# markIII_adapter.net
KiCad netlist of a schematic drawn in EAGLE
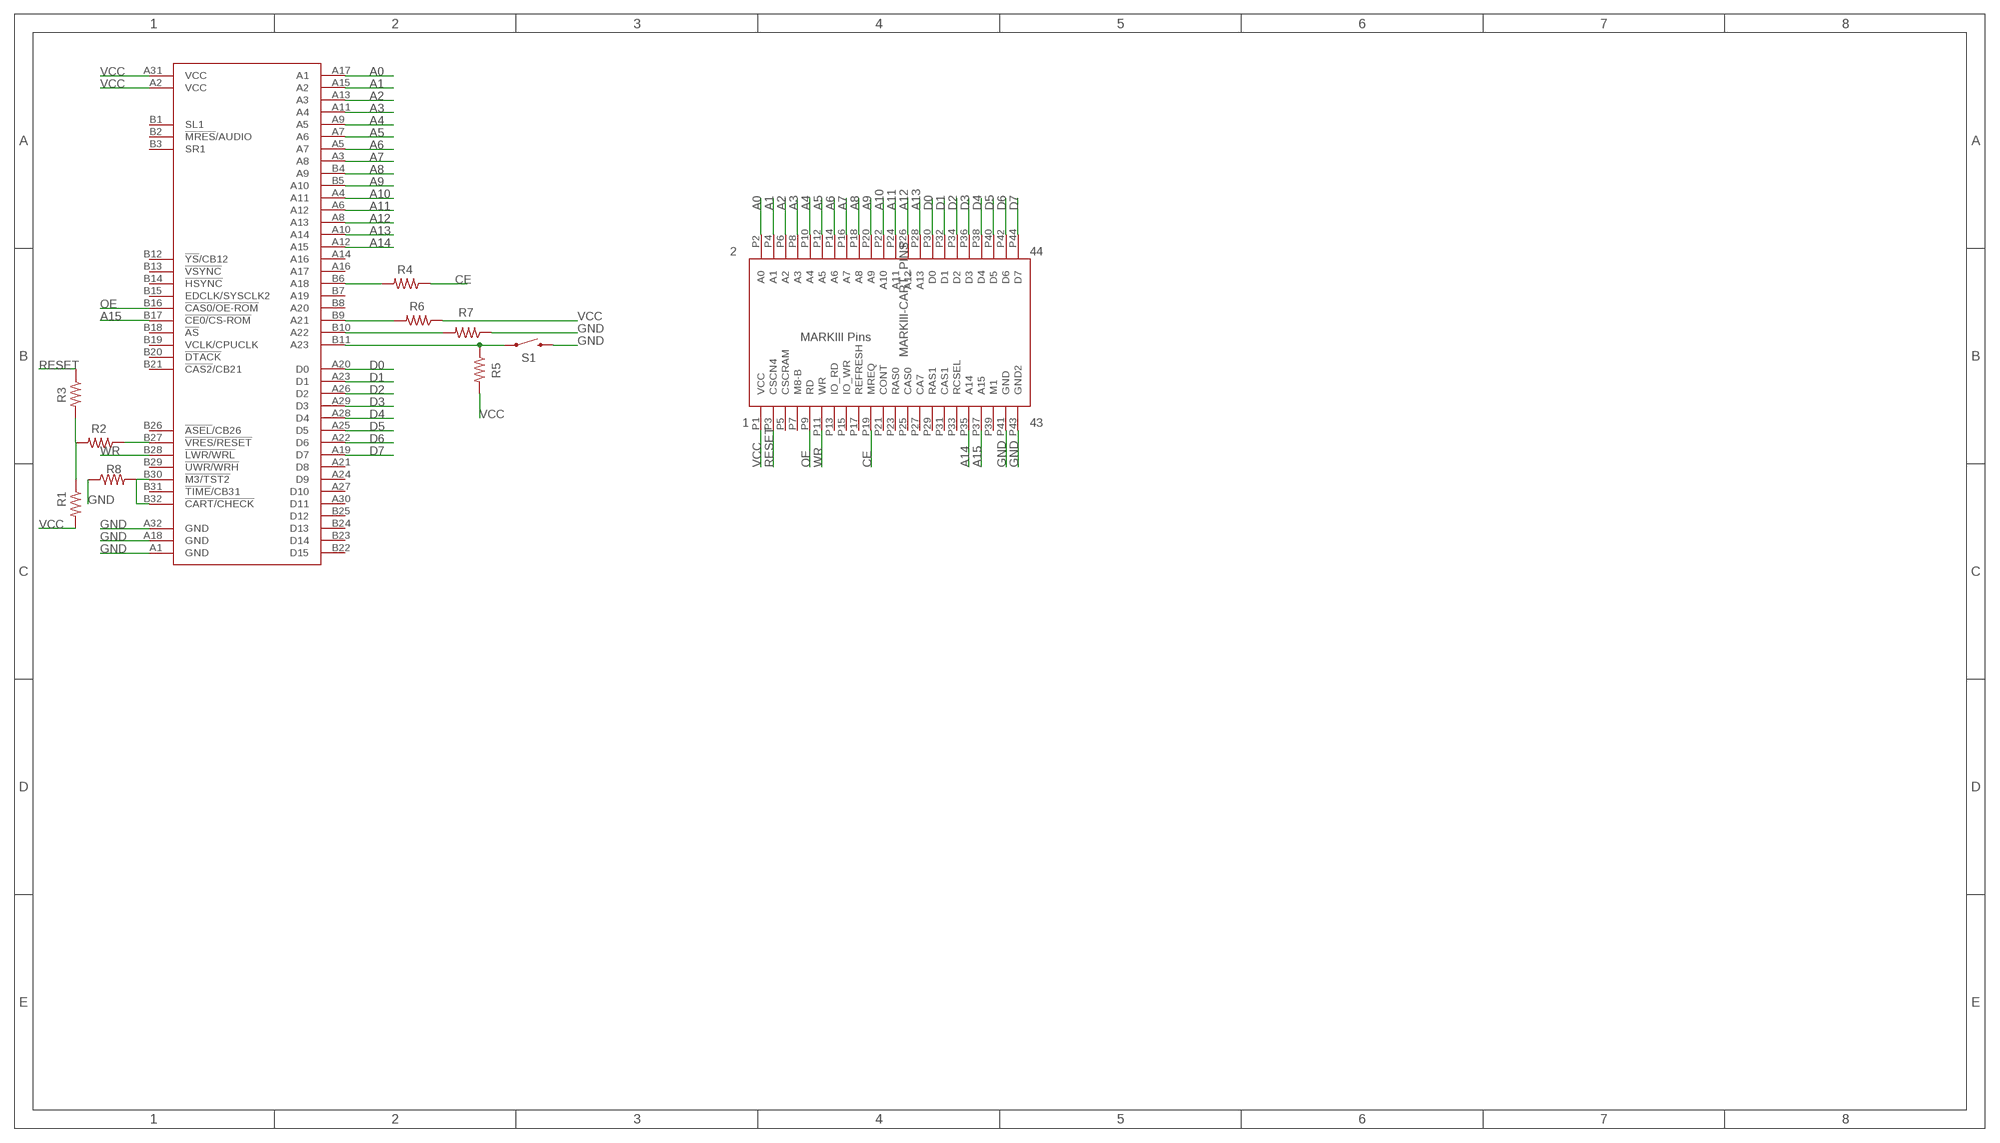
[diagram p0: schematic, sheet 1]

(export (version "E")
  (design (tool "Eeschema 10.0.6"))
  (components
    (comp (ref "CN3")
      (value "MEGADRIVE-CART-CONNECTOR-ORDERED")
      (footprint "eagle-import:MEGADRIVE-CART-CONNECTOR")
      (libsource (lib "eagle-import") (part "MEGADRIVE-CART-CONNECTOR-ORDERED"))
    )
    (comp (ref "R1")
      (value "0")
      (footprint "eagle-import:M1206")
      (libsource (lib "eagle-import") (part "R-US_M1206"))
    )
    (comp (ref "R2")
      (value "NP")
      (footprint "eagle-import:M1206")
      (libsource (lib "eagle-import") (part "R-US_M1206"))
    )
    (comp (ref "R3")
      (value "NP")
      (footprint "eagle-import:M1206")
      (libsource (lib "eagle-import") (part "R-US_M1206"))
    )
    (comp (ref "R4")
      (value "0")
      (footprint "eagle-import:M1206")
      (libsource (lib "eagle-import") (part "R-US_M1206"))
    )
    (comp (ref "R5")
      (value "56K")
      (footprint "eagle-import:M1206")
      (libsource (lib "eagle-import") (part "R-US_M1206"))
    )
    (comp (ref "R6")
      (value "0")
      (footprint "eagle-import:M1206")
      (libsource (lib "eagle-import") (part "R-US_M1206"))
    )
    (comp (ref "R7")
      (value "0")
      (footprint "eagle-import:M1206")
      (libsource (lib "eagle-import") (part "R-US_M1206"))
    )
    (comp (ref "R8")
      (value "0")
      (footprint "eagle-import:M1206")
      (libsource (lib "eagle-import") (part "R-US_M1206"))
    )
    (comp (ref "S1")
      (value "MOMENTARY-SWITCH-SPST-SMD-5.2MM")
      (footprint "eagle-import:TACTILE_SWITCH_SMD_5.2MM")
      (libsource (lib "eagle-import") (part "MOMENTARY-SWITCH-SPST-SMD-5.2MM"))
    )
    (comp (ref "U$1")
      (value "MARKIII-CART_PINS")
      (footprint "eagle-import:MARKIII_PINS")
      (libsource (lib "eagle-import") (part "MARKIII-CART_PINS"))
    )
  )
  (nets
    (net (code "1") (name "/A0") (class "Default")
      (node (ref "CN3") (pin "A17") (pinfunction "A1_A17") (pintype "bidirectional"))
      (node (ref "U$1") (pin "P2") (pinfunction "A0_P2") (pintype "bidirectional"))
    )
    (net (code "2") (name "/A1") (class "Default")
      (node (ref "CN3") (pin "A15") (pinfunction "A2_A15") (pintype "bidirectional"))
      (node (ref "U$1") (pin "P4") (pinfunction "A1_P4") (pintype "bidirectional"))
    )
    (net (code "3") (name "/A2") (class "Default")
      (node (ref "CN3") (pin "A13") (pinfunction "A3_A13") (pintype "bidirectional"))
      (node (ref "U$1") (pin "P6") (pinfunction "A2_P6") (pintype "bidirectional"))
    )
    (net (code "4") (name "/A3") (class "Default")
      (node (ref "CN3") (pin "A11") (pinfunction "A4_A11") (pintype "bidirectional"))
      (node (ref "U$1") (pin "P8") (pinfunction "A3_P8") (pintype "bidirectional"))
    )
    (net (code "5") (name "/A4") (class "Default")
      (node (ref "CN3") (pin "A9") (pinfunction "A5_A9") (pintype "bidirectional"))
      (node (ref "U$1") (pin "P10") (pinfunction "A4_P10") (pintype "bidirectional"))
    )
    (net (code "6") (name "/A5") (class "Default")
      (node (ref "CN3") (pin "A7") (pinfunction "A6_A7") (pintype "bidirectional"))
      (node (ref "U$1") (pin "P12") (pinfunction "A5_P12") (pintype "bidirectional"))
    )
    (net (code "7") (name "/A6") (class "Default")
      (node (ref "CN3") (pin "A5") (pinfunction "A7_A5") (pintype "bidirectional"))
      (node (ref "U$1") (pin "P14") (pinfunction "A6_P14") (pintype "bidirectional"))
    )
    (net (code "8") (name "/A7") (class "Default")
      (node (ref "CN3") (pin "A3") (pinfunction "A8_A3") (pintype "bidirectional"))
      (node (ref "U$1") (pin "P16") (pinfunction "A7_P16") (pintype "bidirectional"))
    )
    (net (code "9") (name "/A8") (class "Default")
      (node (ref "CN3") (pin "B4") (pinfunction "A9_B4") (pintype "bidirectional"))
      (node (ref "U$1") (pin "P18") (pinfunction "A8_P18") (pintype "bidirectional"))
    )
    (net (code "10") (name "/A9") (class "Default")
      (node (ref "CN3") (pin "B5") (pinfunction "A10_B5") (pintype "bidirectional"))
      (node (ref "U$1") (pin "P20") (pinfunction "A9_P20") (pintype "bidirectional"))
    )
    (net (code "11") (name "/A10") (class "Default")
      (node (ref "CN3") (pin "A4") (pinfunction "A11_A4") (pintype "bidirectional"))
      (node (ref "U$1") (pin "P22") (pinfunction "A10_P22") (pintype "bidirectional"))
    )
    (net (code "12") (name "/A11") (class "Default")
      (node (ref "CN3") (pin "A6") (pinfunction "A12_A6") (pintype "bidirectional"))
      (node (ref "U$1") (pin "P24") (pinfunction "A11_P24") (pintype "bidirectional"))
    )
    (net (code "13") (name "/A12") (class "Default")
      (node (ref "CN3") (pin "A8") (pinfunction "A13_A8") (pintype "bidirectional"))
      (node (ref "U$1") (pin "P26") (pinfunction "A12_P26") (pintype "bidirectional"))
    )
    (net (code "14") (name "/A13") (class "Default")
      (node (ref "CN3") (pin "A10") (pinfunction "A14_A10") (pintype "bidirectional"))
      (node (ref "U$1") (pin "P28") (pinfunction "A13_P28") (pintype "bidirectional"))
    )
    (net (code "15") (name "/A14") (class "Default")
      (node (ref "CN3") (pin "A12") (pinfunction "A15_A12") (pintype "bidirectional"))
      (node (ref "U$1") (pin "P35") (pinfunction "A14_P35") (pintype "bidirectional"))
    )
    (net (code "16") (name "/A15") (class "Default")
      (node (ref "CN3") (pin "B17") (pinfunction "~{CE0/CS-ROM}_B17") (pintype "bidirectional"))
      (node (ref "U$1") (pin "P37") (pinfunction "A15_P37") (pintype "bidirectional"))
    )
    (net (code "17") (name "/CE") (class "Default")
      (node (ref "R4") (pin "1") (pinfunction "1_1") (pintype "passive"))
      (node (ref "U$1") (pin "P19") (pinfunction "MREQ_P19") (pintype "bidirectional"))
    )
    (net (code "18") (name "/D0") (class "Default")
      (node (ref "CN3") (pin "A20") (pinfunction "D0_A20") (pintype "bidirectional"))
      (node (ref "U$1") (pin "P30") (pinfunction "D0_P30") (pintype "bidirectional"))
    )
    (net (code "19") (name "/D1") (class "Default")
      (node (ref "CN3") (pin "A23") (pinfunction "D1_A23") (pintype "bidirectional"))
      (node (ref "U$1") (pin "P32") (pinfunction "D1_P32") (pintype "bidirectional"))
    )
    (net (code "20") (name "/D2") (class "Default")
      (node (ref "CN3") (pin "A26") (pinfunction "D2_A26") (pintype "bidirectional"))
      (node (ref "U$1") (pin "P34") (pinfunction "D2_P34") (pintype "bidirectional"))
    )
    (net (code "21") (name "/D3") (class "Default")
      (node (ref "CN3") (pin "A29") (pinfunction "D3_A29") (pintype "bidirectional"))
      (node (ref "U$1") (pin "P36") (pinfunction "D3_P36") (pintype "bidirectional"))
    )
    (net (code "22") (name "/D4") (class "Default")
      (node (ref "CN3") (pin "A28") (pinfunction "D4_A28") (pintype "bidirectional"))
      (node (ref "U$1") (pin "P38") (pinfunction "D4_P38") (pintype "bidirectional"))
    )
    (net (code "23") (name "/D5") (class "Default")
      (node (ref "CN3") (pin "A25") (pinfunction "D5_A25") (pintype "bidirectional"))
      (node (ref "U$1") (pin "P40") (pinfunction "D5_P40") (pintype "bidirectional"))
    )
    (net (code "24") (name "/D6") (class "Default")
      (node (ref "CN3") (pin "A22") (pinfunction "D6_A22") (pintype "bidirectional"))
      (node (ref "U$1") (pin "P42") (pinfunction "D6_P42") (pintype "bidirectional"))
    )
    (net (code "25") (name "/D7") (class "Default")
      (node (ref "CN3") (pin "A19") (pinfunction "D7_A19") (pintype "bidirectional"))
      (node (ref "U$1") (pin "P44") (pinfunction "D7_P44") (pintype "bidirectional"))
    )
    (net (code "26") (name "/GND") (class "Default")
      (node (ref "CN3") (pin "A1") (pinfunction "GND_A1") (pintype "bidirectional"))
      (node (ref "CN3") (pin "A18") (pinfunction "GND_A18") (pintype "bidirectional"))
      (node (ref "CN3") (pin "A32") (pinfunction "GND_A32") (pintype "bidirectional"))
      (node (ref "R7") (pin "1") (pinfunction "1_1") (pintype "passive"))
      (node (ref "R8") (pin "1") (pinfunction "1_1") (pintype "passive"))
      (node (ref "S1") (pin "3") (pinfunction "2_3") (pintype "passive"))
      (node (ref "U$1") (pin "P41") (pinfunction "GND_P41") (pintype "bidirectional"))
      (node (ref "U$1") (pin "P43") (pinfunction "GND2_P43") (pintype "bidirectional"))
    )
    (net (code "27") (name "/OE") (class "Default")
      (node (ref "CN3") (pin "B16") (pinfunction "~{CAS0/OE-ROM}_B16") (pintype "bidirectional"))
      (node (ref "U$1") (pin "P9") (pinfunction "RD_P9") (pintype "bidirectional"))
    )
    (net (code "28") (name "/RESET") (class "Default")
      (node (ref "R3") (pin "1") (pinfunction "1_1") (pintype "passive"))
      (node (ref "U$1") (pin "P3") (pinfunction "CSCN4_P3") (pintype "bidirectional"))
    )
    (net (code "29") (name "/VCC") (class "Default")
      (node (ref "CN3") (pin "A2") (pinfunction "VCC_A2") (pintype "bidirectional"))
      (node (ref "CN3") (pin "A31") (pinfunction "VCC_A31") (pintype "bidirectional"))
      (node (ref "R1") (pin "2") (pinfunction "2_2") (pintype "passive"))
      (node (ref "R5") (pin "2") (pinfunction "2_2") (pintype "passive"))
      (node (ref "R6") (pin "1") (pinfunction "1_1") (pintype "passive"))
      (node (ref "U$1") (pin "P1") (pinfunction "VCC_P1") (pintype "bidirectional"))
    )
    (net (code "30") (name "/WR") (class "Default")
      (node (ref "CN3") (pin "B28") (pinfunction "~{LWR/WRL}_B28") (pintype "bidirectional"))
      (node (ref "U$1") (pin "P11") (pinfunction "WR_P11") (pintype "bidirectional"))
    )
    (net (code "31") (name "Net-(CN3-A18)") (class "Default")
      (node (ref "CN3") (pin "B6") (pinfunction "A18_B6") (pintype "bidirectional"))
      (node (ref "R4") (pin "2") (pinfunction "2_2") (pintype "passive"))
    )
    (net (code "32") (name "Net-(CN3-A21)") (class "Default")
      (node (ref "CN3") (pin "B9") (pinfunction "A21_B9") (pintype "bidirectional"))
      (node (ref "R6") (pin "2") (pinfunction "2_2") (pintype "passive"))
    )
    (net (code "33") (name "Net-(CN3-A22)") (class "Default")
      (node (ref "CN3") (pin "B10") (pinfunction "A22_B10") (pintype "bidirectional"))
      (node (ref "R7") (pin "2") (pinfunction "2_2") (pintype "passive"))
    )
    (net (code "34") (name "Net-(CN3-A23)") (class "Default")
      (node (ref "CN3") (pin "B11") (pinfunction "A23_B11") (pintype "bidirectional"))
      (node (ref "R5") (pin "1") (pinfunction "1_1") (pintype "passive"))
      (node (ref "S1") (pin "1") (pinfunction "1_1") (pintype "passive"))
    )
    (net (code "35") (name "Net-(CN3-~{CART{slash}CHECK})") (class "Default")
      (node (ref "CN3") (pin "B30") (pinfunction "~{M3/TST2}_B30") (pintype "bidirectional"))
      (node (ref "CN3") (pin "B32") (pinfunction "~{CART/CHECK}_B32") (pintype "bidirectional"))
      (node (ref "R8") (pin "2") (pinfunction "2_2") (pintype "passive"))
    )
    (net (code "36") (name "Net-(CN3-~{VRES{slash}RESET})") (class "Default")
      (node (ref "CN3") (pin "B27") (pinfunction "~{VRES/RESET}_B27") (pintype "bidirectional"))
      (node (ref "R2") (pin "1") (pinfunction "1_1") (pintype "passive"))
    )
    (net (code "37") (name "Net-(R1-Pad1)") (class "Default")
      (node (ref "R1") (pin "1") (pinfunction "1_1") (pintype "passive"))
      (node (ref "R2") (pin "2") (pinfunction "2_2") (pintype "passive"))
      (node (ref "R3") (pin "2") (pinfunction "2_2") (pintype "passive"))
    )
    (net (code "38") (name "unconnected-(CN3-A16-PadA14)") (class "Default")
      (node (ref "CN3") (pin "A14") (pinfunction "A16_A14") (pintype "bidirectional"))
    )
    (net (code "39") (name "unconnected-(CN3-A17-PadA16)") (class "Default")
      (node (ref "CN3") (pin "A16") (pinfunction "A17_A16") (pintype "bidirectional"))
    )
    (net (code "40") (name "unconnected-(CN3-A19-PadB7)") (class "Default")
      (node (ref "CN3") (pin "B7") (pinfunction "A19_B7") (pintype "bidirectional"))
    )
    (net (code "41") (name "unconnected-(CN3-A20-PadB8)") (class "Default")
      (node (ref "CN3") (pin "B8") (pinfunction "A20_B8") (pintype "bidirectional"))
    )
    (net (code "42") (name "unconnected-(CN3-D8-PadA21)") (class "Default")
      (node (ref "CN3") (pin "A21") (pinfunction "D8_A21") (pintype "bidirectional"))
    )
    (net (code "43") (name "unconnected-(CN3-D9-PadA24)") (class "Default")
      (node (ref "CN3") (pin "A24") (pinfunction "D9_A24") (pintype "bidirectional"))
    )
    (net (code "44") (name "unconnected-(CN3-D10-PadA27)") (class "Default")
      (node (ref "CN3") (pin "A27") (pinfunction "D10_A27") (pintype "bidirectional"))
    )
    (net (code "45") (name "unconnected-(CN3-D11-PadA30)") (class "Default")
      (node (ref "CN3") (pin "A30") (pinfunction "D11_A30") (pintype "bidirectional"))
    )
    (net (code "46") (name "unconnected-(CN3-D12-PadB25)") (class "Default")
      (node (ref "CN3") (pin "B25") (pinfunction "D12_B25") (pintype "bidirectional"))
    )
    (net (code "47") (name "unconnected-(CN3-D13-PadB24)") (class "Default")
      (node (ref "CN3") (pin "B24") (pinfunction "D13_B24") (pintype "bidirectional"))
    )
    (net (code "48") (name "unconnected-(CN3-D14-PadB23)") (class "Default")
      (node (ref "CN3") (pin "B23") (pinfunction "D14_B23") (pintype "bidirectional"))
    )
    (net (code "49") (name "unconnected-(CN3-D15-PadB22)") (class "Default")
      (node (ref "CN3") (pin "B22") (pinfunction "D15_B22") (pintype "bidirectional"))
    )
    (net (code "50") (name "unconnected-(CN3-EDCLK{slash}SYSCLK2-PadB15)") (class "Default")
      (node (ref "CN3") (pin "B15") (pinfunction "EDCLK/SYSCLK2_B15") (pintype "bidirectional"))
    )
    (net (code "51") (name "unconnected-(CN3-SL1-PadB1)") (class "Default")
      (node (ref "CN3") (pin "B1") (pinfunction "SL1_B1") (pintype "bidirectional"))
    )
    (net (code "52") (name "unconnected-(CN3-SR1-PadB3)") (class "Default")
      (node (ref "CN3") (pin "B3") (pinfunction "SR1_B3") (pintype "bidirectional"))
    )
    (net (code "53") (name "unconnected-(CN3-VCLK{slash}CPUCLK-PadB19)") (class "Default")
      (node (ref "CN3") (pin "B19") (pinfunction "VCLK/CPUCLK_B19") (pintype "bidirectional"))
    )
    (net (code "54") (name "unconnected-(CN3-~{ASEL}{slash}CB26-PadB26)") (class "Default")
      (node (ref "CN3") (pin "B26") (pinfunction "~{ASEL}/CB26_B26") (pintype "bidirectional"))
    )
    (net (code "55") (name "unconnected-(CN3-~{AS}-PadB18)") (class "Default")
      (node (ref "CN3") (pin "B18") (pinfunction "~{AS}_B18") (pintype "bidirectional"))
    )
    (net (code "56") (name "unconnected-(CN3-~{CAS2}{slash}CB21-PadB21)") (class "Default")
      (node (ref "CN3") (pin "B21") (pinfunction "~{CAS2}/CB21_B21") (pintype "bidirectional"))
    )
    (net (code "57") (name "unconnected-(CN3-~{DTACK}-PadB20)") (class "Default")
      (node (ref "CN3") (pin "B20") (pinfunction "~{DTACK}_B20") (pintype "bidirectional"))
    )
    (net (code "58") (name "unconnected-(CN3-~{HSYNC}-PadB14)") (class "Default")
      (node (ref "CN3") (pin "B14") (pinfunction "~{HSYNC}_B14") (pintype "bidirectional"))
    )
    (net (code "59") (name "unconnected-(CN3-~{MRES}{slash}AUDIO-PadB2)") (class "Default")
      (node (ref "CN3") (pin "B2") (pinfunction "~{MRES}/AUDIO_B2") (pintype "bidirectional"))
    )
    (net (code "60") (name "unconnected-(CN3-~{TIME}{slash}CB31-PadB31)") (class "Default")
      (node (ref "CN3") (pin "B31") (pinfunction "~{TIME}/CB31_B31") (pintype "bidirectional"))
    )
    (net (code "61") (name "unconnected-(CN3-~{UWR{slash}WRH}-PadB29)") (class "Default")
      (node (ref "CN3") (pin "B29") (pinfunction "~{UWR/WRH}_B29") (pintype "bidirectional"))
    )
    (net (code "62") (name "unconnected-(CN3-~{VSYNC}-PadB13)") (class "Default")
      (node (ref "CN3") (pin "B13") (pinfunction "~{VSYNC}_B13") (pintype "bidirectional"))
    )
    (net (code "63") (name "unconnected-(CN3-~{YS}{slash}CB12-PadB12)") (class "Default")
      (node (ref "CN3") (pin "B12") (pinfunction "~{YS}/CB12_B12") (pintype "bidirectional"))
    )
    (net (code "64") (name "unconnected-(U$1-CA7-PadP27)") (class "Default")
      (node (ref "U$1") (pin "P27") (pinfunction "CA7_P27") (pintype "bidirectional"))
    )
    (net (code "65") (name "unconnected-(U$1-CAS0-PadP25)") (class "Default")
      (node (ref "U$1") (pin "P25") (pinfunction "CAS0_P25") (pintype "bidirectional"))
    )
    (net (code "66") (name "unconnected-(U$1-CAS1-PadP31)") (class "Default")
      (node (ref "U$1") (pin "P31") (pinfunction "CAS1_P31") (pintype "bidirectional"))
    )
    (net (code "67") (name "unconnected-(U$1-CONT-PadP21)") (class "Default")
      (node (ref "U$1") (pin "P21") (pinfunction "CONT_P21") (pintype "bidirectional"))
    )
    (net (code "68") (name "unconnected-(U$1-CSCRAM-PadP5)") (class "Default")
      (node (ref "U$1") (pin "P5") (pinfunction "CSCRAM_P5") (pintype "bidirectional"))
    )
    (net (code "69") (name "unconnected-(U$1-IO_RD-PadP13)") (class "Default")
      (node (ref "U$1") (pin "P13") (pinfunction "IO_RD_P13") (pintype "bidirectional"))
    )
    (net (code "70") (name "unconnected-(U$1-IO_WR-PadP15)") (class "Default")
      (node (ref "U$1") (pin "P15") (pinfunction "IO_WR_P15") (pintype "bidirectional"))
    )
    (net (code "71") (name "unconnected-(U$1-M1-PadP39)") (class "Default")
      (node (ref "U$1") (pin "P39") (pinfunction "M1_P39") (pintype "bidirectional"))
    )
    (net (code "72") (name "unconnected-(U$1-M8-B-PadP7)") (class "Default")
      (node (ref "U$1") (pin "P7") (pinfunction "M8-B_P7") (pintype "bidirectional"))
    )
    (net (code "73") (name "unconnected-(U$1-RAS0-PadP23)") (class "Default")
      (node (ref "U$1") (pin "P23") (pinfunction "RAS0_P23") (pintype "bidirectional"))
    )
    (net (code "74") (name "unconnected-(U$1-RAS1-PadP29)") (class "Default")
      (node (ref "U$1") (pin "P29") (pinfunction "RAS1_P29") (pintype "bidirectional"))
    )
    (net (code "75") (name "unconnected-(U$1-RCSEL-PadP33)") (class "Default")
      (node (ref "U$1") (pin "P33") (pinfunction "RCSEL_P33") (pintype "bidirectional"))
    )
    (net (code "76") (name "unconnected-(U$1-REFRESH-PadP17)") (class "Default")
      (node (ref "U$1") (pin "P17") (pinfunction "REFRESH_P17") (pintype "bidirectional"))
    )
  )
)
